# 08_Peripherals.net
KiCad netlist of a schematic drawn in Altium Designer
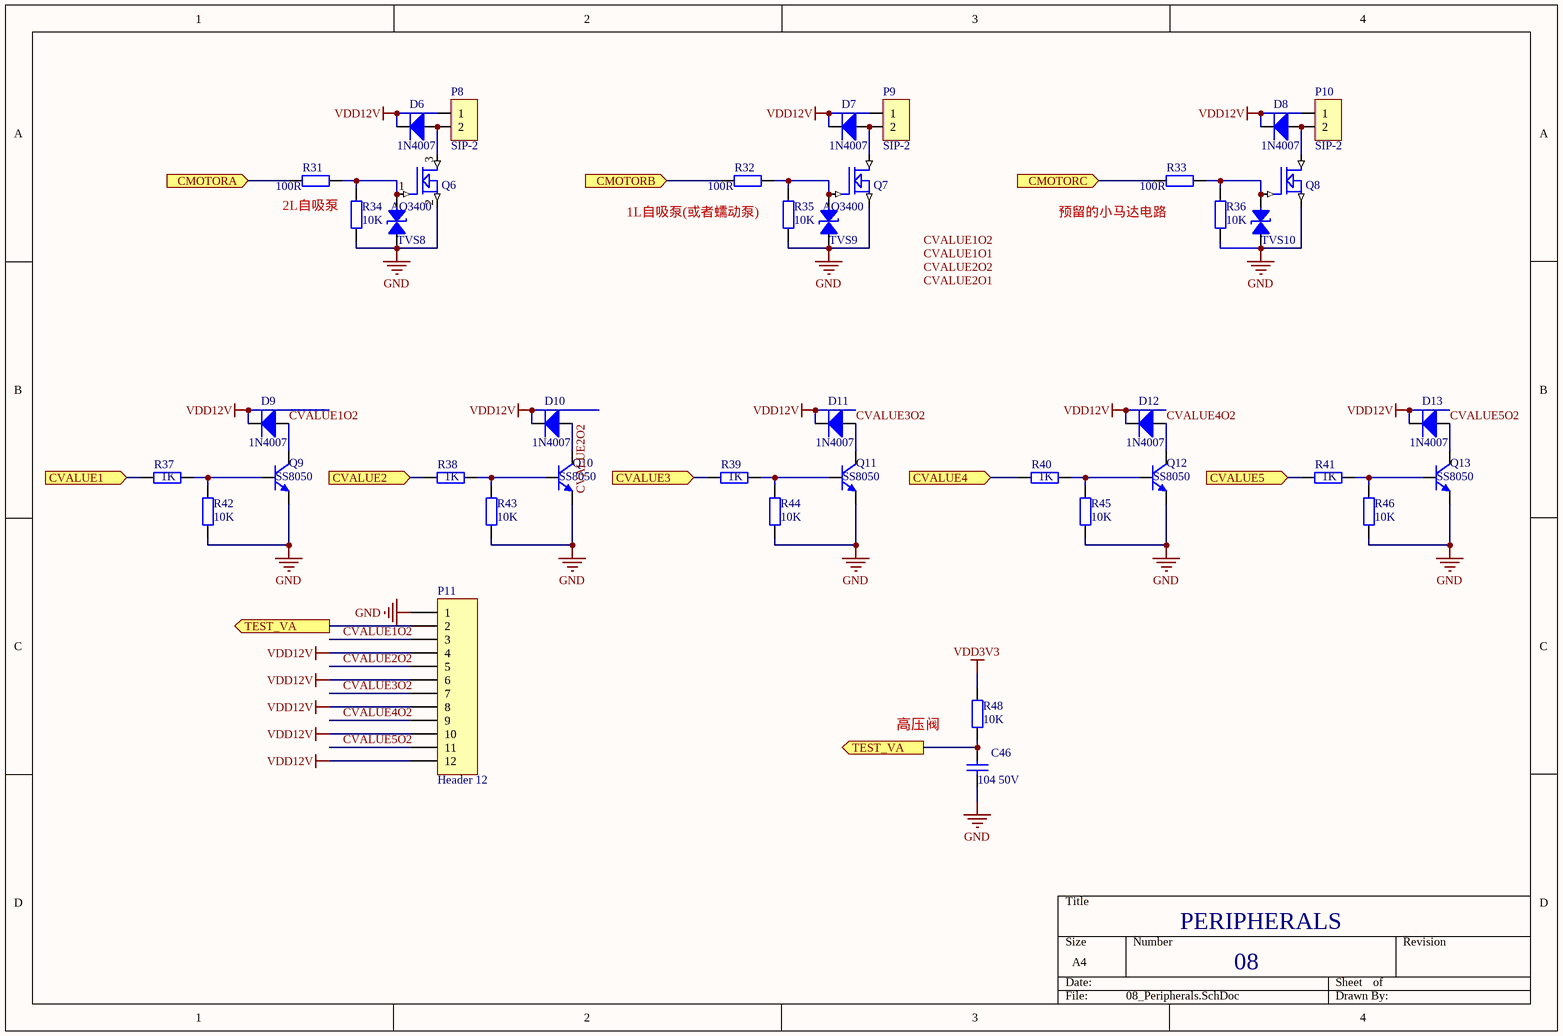
[diagram p0: 08_Peripherals.SchDoc]

(export (version "E")
  (design (tool "Eeschema 10.0.6"))
  (components
    (comp (ref "C46")
      (value "104 50V")
      (footprint "SMD-0603C")
      (description "贴片电容 10%")
      (libsource (lib "XiaoyI") (part "CAP4"))
    )
    (comp (ref "D6")
      (value "1N4007")
      (footprint "DO-214-AC")
      (description "贴片二极管")
      (libsource (lib "XiaoyI") (part "DIODE2"))
    )
    (comp (ref "D7")
      (value "1N4007")
      (footprint "DO-214-AC")
      (description "贴片二极管")
      (libsource (lib "XiaoyI") (part "DIODE2"))
    )
    (comp (ref "D8")
      (value "1N4007")
      (footprint "DO-214-AC")
      (description "贴片二极管")
      (libsource (lib "XiaoyI") (part "DIODE2"))
    )
    (comp (ref "D9")
      (value "1N4007")
      (footprint "DO-214-AC")
      (description "贴片二极管")
      (libsource (lib "XiaoyI") (part "DIODE2"))
    )
    (comp (ref "D10")
      (value "1N4007")
      (footprint "DO-214-AC")
      (description "贴片二极管")
      (libsource (lib "XiaoyI") (part "DIODE2"))
    )
    (comp (ref "D11")
      (value "1N4007")
      (footprint "DO-214-AC")
      (description "贴片二极管")
      (libsource (lib "XiaoyI") (part "DIODE2"))
    )
    (comp (ref "D12")
      (value "1N4007")
      (footprint "DO-214-AC")
      (description "贴片二极管")
      (libsource (lib "XiaoyI") (part "DIODE2"))
    )
    (comp (ref "D13")
      (value "1N4007")
      (footprint "DO-214-AC")
      (description "贴片二极管")
      (libsource (lib "XiaoyI") (part "DIODE2"))
    )
    (comp (ref "P8")
      (value "SIP-2")
      (footprint "SIP-2A")
      (description "XH2.54 2P 立贴")
      (libsource (lib "XiaoyI") (part "SIP-2"))
    )
    (comp (ref "P9")
      (value "SIP-2")
      (footprint "SIP-2A")
      (description "XH2.54 2P 立贴")
      (libsource (lib "XiaoyI") (part "SIP-2"))
    )
    (comp (ref "P10")
      (value "SIP-2")
      (footprint "SIP-2A")
      (description "XH2.54 2P 立贴")
      (libsource (lib "XiaoyI") (part "SIP-2"))
    )
    (comp (ref "P11")
      (value "Header 12")
      (footprint "12X2.54MMZ")
      (description "Header, 12-Pin")
      (fields (field (name "PUBLISHER") "Altium Limited"))
      (libsource (lib "Miscellaneous Connectors") (part "Header 12"))
    )
    (comp (ref "Q6")
      (value "AO3400")
      (footprint "SOT-23")
      (description "MOSFET N")
      (libsource (lib "XiaoyI") (part "MOSFET N"))
    )
    (comp (ref "Q7")
      (value "AO3400")
      (footprint "SOT-23")
      (description "MOSFET N")
      (libsource (lib "") (part "MOSFET N_1"))
    )
    (comp (ref "Q8")
      (value "AO3400")
      (footprint "SOT-23")
      (description "MOSFET N")
      (libsource (lib "") (part "MOSFET N_1"))
    )
    (comp (ref "Q9")
      (value "SS8050")
      (footprint "SOT-23")
      (description "三极管")
      (libsource (lib "XiaoyI") (part "NPN-1"))
    )
    (comp (ref "Q10")
      (value "SS8050")
      (footprint "SOT-23")
      (description "三极管")
      (libsource (lib "XiaoyI") (part "NPN-1"))
    )
    (comp (ref "Q11")
      (value "SS8050")
      (footprint "SOT-23")
      (description "三极管")
      (libsource (lib "XiaoyI") (part "NPN-1"))
    )
    (comp (ref "Q12")
      (value "SS8050")
      (footprint "SOT-23")
      (description "三极管")
      (libsource (lib "XiaoyI") (part "NPN-1"))
    )
    (comp (ref "Q13")
      (value "SS8050")
      (footprint "SOT-23")
      (description "三极管")
      (libsource (lib "XiaoyI") (part "NPN-1"))
    )
    (comp (ref "R31")
      (value "100R")
      (footprint "SMD-0603")
      (description "贴片电阻 5%")
      (libsource (lib "XiaoyI") (part "RES-SOP"))
    )
    (comp (ref "R32")
      (value "100R")
      (footprint "SMD-0603")
      (description "贴片电阻 5%")
      (libsource (lib "XiaoyI") (part "RES-SOP"))
    )
    (comp (ref "R33")
      (value "100R")
      (footprint "SMD-0603")
      (description "贴片电阻 5%")
      (libsource (lib "XiaoyI") (part "RES-SOP"))
    )
    (comp (ref "R34")
      (value "10K")
      (footprint "SMD-0603")
      (description "贴片电阻 5%")
      (libsource (lib "") (part "RES-SOP_1"))
    )
    (comp (ref "R35")
      (value "10K")
      (footprint "SMD-0603")
      (description "贴片电阻 5%")
      (libsource (lib "") (part "RES-SOP_1"))
    )
    (comp (ref "R36")
      (value "10K")
      (footprint "SMD-0603")
      (description "贴片电阻 5%")
      (libsource (lib "") (part "RES-SOP_1"))
    )
    (comp (ref "R37")
      (value "1K")
      (footprint "SMD-0603")
      (description "贴片电阻 5%")
      (libsource (lib "XiaoyI") (part "RES-SOP"))
    )
    (comp (ref "R38")
      (value "1K")
      (footprint "SMD-0603")
      (description "贴片电阻 5%")
      (libsource (lib "XiaoyI") (part "RES-SOP"))
    )
    (comp (ref "R39")
      (value "1K")
      (footprint "SMD-0603")
      (description "贴片电阻 5%")
      (libsource (lib "XiaoyI") (part "RES-SOP"))
    )
    (comp (ref "R40")
      (value "1K")
      (footprint "SMD-0603")
      (description "贴片电阻 5%")
      (libsource (lib "XiaoyI") (part "RES-SOP"))
    )
    (comp (ref "R41")
      (value "1K")
      (footprint "SMD-0603")
      (description "贴片电阻 5%")
      (libsource (lib "XiaoyI") (part "RES-SOP"))
    )
    (comp (ref "R42")
      (value "10K")
      (footprint "SMD-0603")
      (description "贴片电阻 5%")
      (libsource (lib "") (part "RES-SOP_1"))
    )
    (comp (ref "R43")
      (value "10K")
      (footprint "SMD-0603")
      (description "贴片电阻 5%")
      (libsource (lib "") (part "RES-SOP_1"))
    )
    (comp (ref "R44")
      (value "10K")
      (footprint "SMD-0603")
      (description "贴片电阻 5%")
      (libsource (lib "") (part "RES-SOP_1"))
    )
    (comp (ref "R45")
      (value "10K")
      (footprint "SMD-0603")
      (description "贴片电阻 5%")
      (libsource (lib "") (part "RES-SOP_1"))
    )
    (comp (ref "R46")
      (value "10K")
      (footprint "SMD-0603")
      (description "贴片电阻 5%")
      (libsource (lib "") (part "RES-SOP_1"))
    )
    (comp (ref "R48")
      (value "10K")
      (footprint "SMD-0603")
      (description "贴片电阻 5%")
      (libsource (lib "") (part "RES-SOP_2"))
    )
    (comp (ref "TVS8")
      (value "ESD5Z5.0CT1G")
      (footprint "SOD-523")
      (description "TVS")
      (libsource (lib "XiaoyI") (part "TVS-1"))
    )
    (comp (ref "TVS9")
      (value "ESD5Z5.0CT1G")
      (footprint "SOD-523")
      (description "TVS")
      (libsource (lib "XiaoyI") (part "TVS-1"))
    )
    (comp (ref "TVS10")
      (value "ESD5Z5.0CT1G")
      (footprint "SOD-523")
      (description "TVS")
      (libsource (lib "XiaoyI") (part "TVS-1"))
    )
  )
  (nets
    (net (code "1") (name "/CMOTORA") (class "Default")
      (node (ref "R31") (pin "2") (pinfunction "2_2") (pintype "passive"))
    )
    (net (code "2") (name "/CMOTORB") (class "Default")
      (node (ref "R32") (pin "2") (pinfunction "2_2") (pintype "passive"))
    )
    (net (code "3") (name "/CMOTORC") (class "Default")
      (node (ref "R33") (pin "2") (pinfunction "2_2") (pintype "passive"))
    )
    (net (code "4") (name "/CVALUE1") (class "Default")
      (node (ref "R37") (pin "2") (pinfunction "2_2") (pintype "passive"))
    )
    (net (code "6") (name "/CVALUE1O2") (class "Default")
      (node (ref "D9") (pin "1") (pinfunction "A_1") (pintype "passive"))
      (node (ref "P11") (pin "3") (pinfunction "3_3") (pintype "passive"))
      (node (ref "Q9") (pin "3") (pinfunction "C_3") (pintype "passive"))
    )
    (net (code "7") (name "/CVALUE2") (class "Default")
      (node (ref "R38") (pin "2") (pinfunction "2_2") (pintype "passive"))
    )
    (net (code "9") (name "/CVALUE2O2") (class "Default")
      (node (ref "D10") (pin "1") (pinfunction "A_1") (pintype "passive"))
      (node (ref "P11") (pin "5") (pinfunction "5_5") (pintype "passive"))
      (node (ref "Q10") (pin "3") (pinfunction "C_3") (pintype "passive"))
    )
    (net (code "10") (name "/CVALUE3") (class "Default")
      (node (ref "R39") (pin "2") (pinfunction "2_2") (pintype "passive"))
    )
    (net (code "11") (name "/CVALUE3O2") (class "Default")
      (node (ref "D11") (pin "1") (pinfunction "A_1") (pintype "passive"))
      (node (ref "P11") (pin "7") (pinfunction "7_7") (pintype "passive"))
      (node (ref "Q11") (pin "3") (pinfunction "C_3") (pintype "passive"))
    )
    (net (code "12") (name "/CVALUE4") (class "Default")
      (node (ref "R40") (pin "2") (pinfunction "2_2") (pintype "passive"))
    )
    (net (code "13") (name "/CVALUE4O2") (class "Default")
      (node (ref "D12") (pin "1") (pinfunction "A_1") (pintype "passive"))
      (node (ref "P11") (pin "9") (pinfunction "9_9") (pintype "passive"))
      (node (ref "Q12") (pin "3") (pinfunction "C_3") (pintype "passive"))
    )
    (net (code "14") (name "/CVALUE5") (class "Default")
      (node (ref "R41") (pin "2") (pinfunction "2_2") (pintype "passive"))
    )
    (net (code "15") (name "/CVALUE5O2") (class "Default")
      (node (ref "D13") (pin "1") (pinfunction "A_1") (pintype "passive"))
      (node (ref "P11") (pin "11") (pinfunction "11_11") (pintype "passive"))
      (node (ref "Q13") (pin "3") (pinfunction "C_3") (pintype "passive"))
    )
    (net (code "16") (name "/TEST_VA") (class "Default")
      (node (ref "C46") (pin "2") (pinfunction "2_2") (pintype "passive"))
      (node (ref "P11") (pin "2") (pinfunction "2_2") (pintype "passive"))
      (node (ref "R48") (pin "1") (pinfunction "1_1") (pintype "passive"))
    )
    (net (code "17") (name "GND") (class "Default")
      (node (ref "C46") (pin "1") (pinfunction "1_1") (pintype "passive"))
      (node (ref "P11") (pin "1") (pinfunction "1_1") (pintype "passive"))
      (node (ref "Q10") (pin "2") (pinfunction "E_2") (pintype "passive"))
      (node (ref "Q11") (pin "2") (pinfunction "E_2") (pintype "passive"))
      (node (ref "Q12") (pin "2") (pinfunction "E_2") (pintype "passive"))
      (node (ref "Q13") (pin "2") (pinfunction "E_2") (pintype "passive"))
      (node (ref "Q6") (pin "2") (pinfunction "S_2") (pintype "output"))
      (node (ref "Q7") (pin "2") (pinfunction "S_2") (pintype "output"))
      (node (ref "Q8") (pin "2") (pinfunction "S_2") (pintype "output"))
      (node (ref "Q9") (pin "2") (pinfunction "E_2") (pintype "passive"))
      (node (ref "R34") (pin "2") (pinfunction "2_2") (pintype "passive"))
      (node (ref "R35") (pin "2") (pinfunction "2_2") (pintype "passive"))
      (node (ref "R36") (pin "2") (pinfunction "2_2") (pintype "passive"))
      (node (ref "R42") (pin "2") (pinfunction "2_2") (pintype "passive"))
      (node (ref "R43") (pin "2") (pinfunction "2_2") (pintype "passive"))
      (node (ref "R44") (pin "2") (pinfunction "2_2") (pintype "passive"))
      (node (ref "R45") (pin "2") (pinfunction "2_2") (pintype "passive"))
      (node (ref "R46") (pin "2") (pinfunction "2_2") (pintype "passive"))
      (node (ref "TVS10") (pin "1") (pinfunction "A_1") (pintype "passive"))
      (node (ref "TVS8") (pin "1") (pinfunction "A_1") (pintype "passive"))
      (node (ref "TVS9") (pin "1") (pinfunction "A_1") (pintype "passive"))
    )
    (net (code "18") (name "Net-(D6-A)") (class "Default")
      (node (ref "D6") (pin "1") (pinfunction "A_1") (pintype "passive"))
      (node (ref "P8") (pin "2") (pinfunction "2_2") (pintype "passive"))
      (node (ref "Q6") (pin "3") (pinfunction "D_3") (pintype "input"))
    )
    (net (code "19") (name "Net-(D7-A)") (class "Default")
      (node (ref "D7") (pin "1") (pinfunction "A_1") (pintype "passive"))
      (node (ref "P9") (pin "2") (pinfunction "2_2") (pintype "passive"))
      (node (ref "Q7") (pin "3") (pinfunction "D_3") (pintype "input"))
    )
    (net (code "20") (name "Net-(D8-A)") (class "Default")
      (node (ref "D8") (pin "1") (pinfunction "A_1") (pintype "passive"))
      (node (ref "P10") (pin "2") (pinfunction "2_2") (pintype "passive"))
      (node (ref "Q8") (pin "3") (pinfunction "D_3") (pintype "input"))
    )
    (net (code "21") (name "Net-(Q6-G)") (class "Default")
      (node (ref "Q6") (pin "1") (pinfunction "G_1") (pintype "input"))
      (node (ref "R31") (pin "1") (pinfunction "1_1") (pintype "passive"))
      (node (ref "R34") (pin "1") (pinfunction "1_1") (pintype "passive"))
      (node (ref "TVS8") (pin "2") (pinfunction "B_2") (pintype "passive"))
    )
    (net (code "22") (name "Net-(Q7-G)") (class "Default")
      (node (ref "Q7") (pin "1") (pinfunction "G_1") (pintype "input"))
      (node (ref "R32") (pin "1") (pinfunction "1_1") (pintype "passive"))
      (node (ref "R35") (pin "1") (pinfunction "1_1") (pintype "passive"))
      (node (ref "TVS9") (pin "2") (pinfunction "B_2") (pintype "passive"))
    )
    (net (code "23") (name "Net-(Q8-G)") (class "Default")
      (node (ref "Q8") (pin "1") (pinfunction "G_1") (pintype "input"))
      (node (ref "R33") (pin "1") (pinfunction "1_1") (pintype "passive"))
      (node (ref "R36") (pin "1") (pinfunction "1_1") (pintype "passive"))
      (node (ref "TVS10") (pin "2") (pinfunction "B_2") (pintype "passive"))
    )
    (net (code "24") (name "Net-(Q9-B)") (class "Default")
      (node (ref "Q9") (pin "1") (pinfunction "B_1") (pintype "passive"))
      (node (ref "R37") (pin "1") (pinfunction "1_1") (pintype "passive"))
      (node (ref "R42") (pin "1") (pinfunction "1_1") (pintype "passive"))
    )
    (net (code "25") (name "Net-(Q10-B)") (class "Default")
      (node (ref "Q10") (pin "1") (pinfunction "B_1") (pintype "passive"))
      (node (ref "R38") (pin "1") (pinfunction "1_1") (pintype "passive"))
      (node (ref "R43") (pin "1") (pinfunction "1_1") (pintype "passive"))
    )
    (net (code "26") (name "Net-(Q11-B)") (class "Default")
      (node (ref "Q11") (pin "1") (pinfunction "B_1") (pintype "passive"))
      (node (ref "R39") (pin "1") (pinfunction "1_1") (pintype "passive"))
      (node (ref "R44") (pin "1") (pinfunction "1_1") (pintype "passive"))
    )
    (net (code "27") (name "Net-(Q12-B)") (class "Default")
      (node (ref "Q12") (pin "1") (pinfunction "B_1") (pintype "passive"))
      (node (ref "R40") (pin "1") (pinfunction "1_1") (pintype "passive"))
      (node (ref "R45") (pin "1") (pinfunction "1_1") (pintype "passive"))
    )
    (net (code "28") (name "Net-(Q13-B)") (class "Default")
      (node (ref "Q13") (pin "1") (pinfunction "B_1") (pintype "passive"))
      (node (ref "R41") (pin "1") (pinfunction "1_1") (pintype "passive"))
      (node (ref "R46") (pin "1") (pinfunction "1_1") (pintype "passive"))
    )
    (net (code "29") (name "VDD3V3") (class "Default")
      (node (ref "R48") (pin "2") (pinfunction "2_2") (pintype "passive"))
    )
    (net (code "30") (name "VDD12V") (class "Default")
      (node (ref "D10") (pin "2") (pinfunction "K_2") (pintype "passive"))
      (node (ref "D11") (pin "2") (pinfunction "K_2") (pintype "passive"))
      (node (ref "D12") (pin "2") (pinfunction "K_2") (pintype "passive"))
      (node (ref "D13") (pin "2") (pinfunction "K_2") (pintype "passive"))
      (node (ref "D6") (pin "2") (pinfunction "K_2") (pintype "passive"))
      (node (ref "D7") (pin "2") (pinfunction "K_2") (pintype "passive"))
      (node (ref "D8") (pin "2") (pinfunction "K_2") (pintype "passive"))
      (node (ref "D9") (pin "2") (pinfunction "K_2") (pintype "passive"))
      (node (ref "P10") (pin "1") (pinfunction "1_1") (pintype "passive"))
      (node (ref "P11") (pin "10") (pinfunction "10_10") (pintype "passive"))
      (node (ref "P11") (pin "12") (pinfunction "12_12") (pintype "passive"))
      (node (ref "P11") (pin "4") (pinfunction "4_4") (pintype "passive"))
      (node (ref "P11") (pin "6") (pinfunction "6_6") (pintype "passive"))
      (node (ref "P11") (pin "8") (pinfunction "8_8") (pintype "passive"))
      (node (ref "P8") (pin "1") (pinfunction "1_1") (pintype "passive"))
      (node (ref "P9") (pin "1") (pinfunction "1_1") (pintype "passive"))
    )
  )
)
